# PixiFlood_1_6_PTH.net
KiCad netlist of a schematic drawn in EAGLE
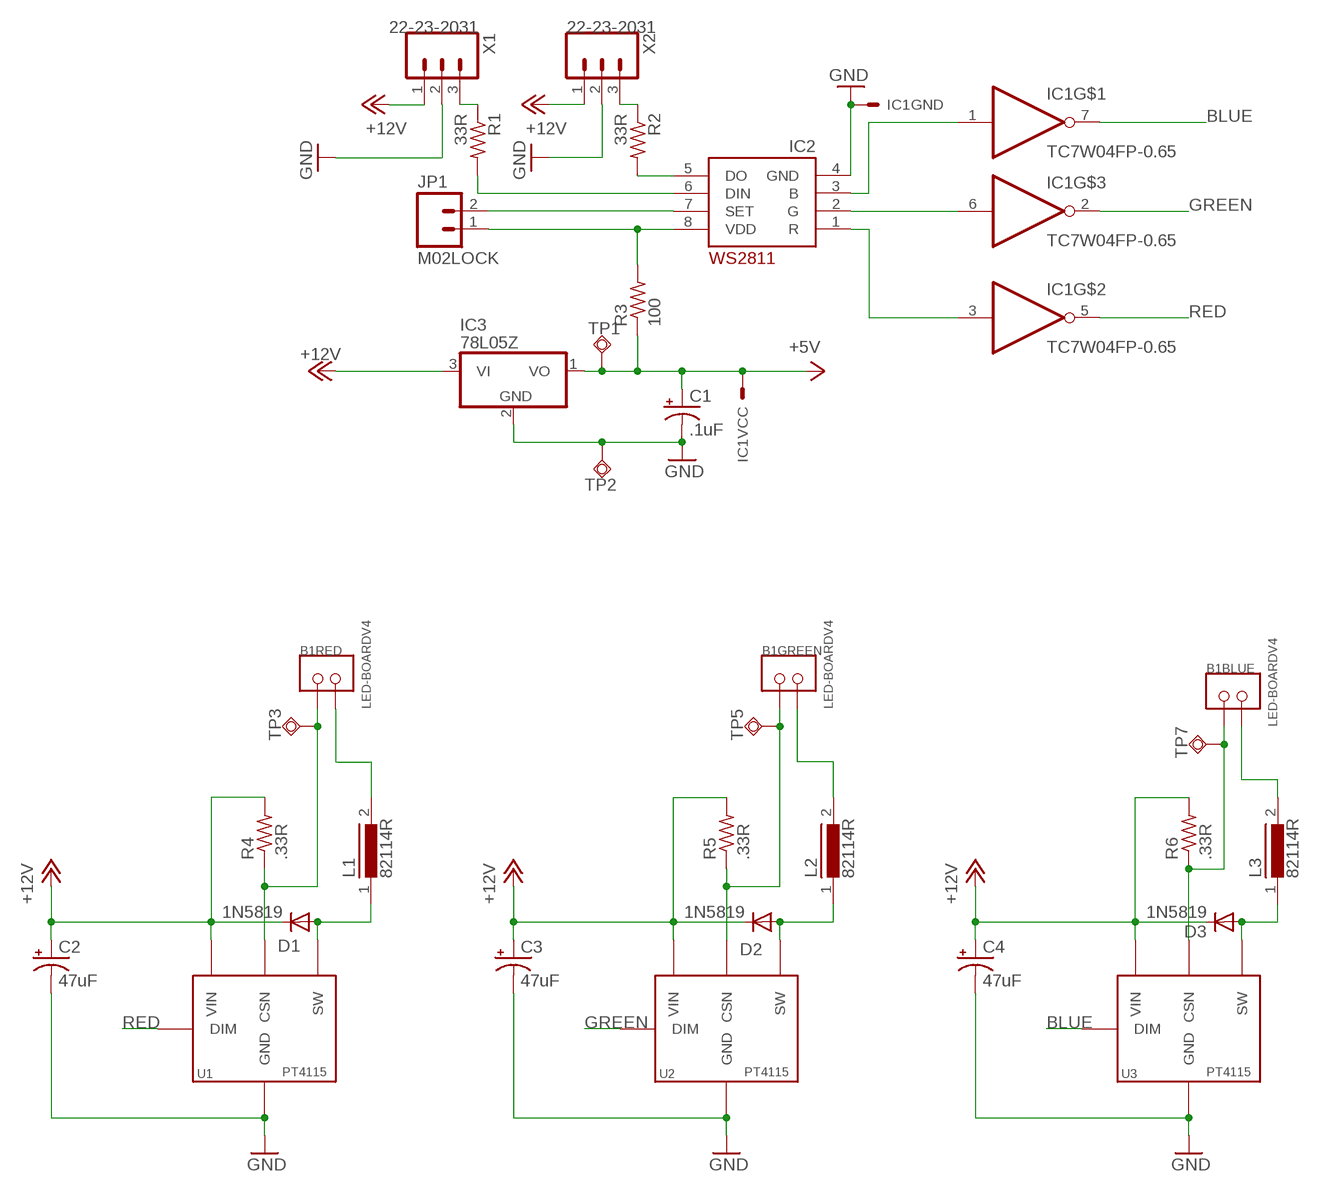
[diagram p0: schematic, sheet 1]

(export (version "E")
  (design (tool "Eeschema 10.0.6"))
  (components
    (comp (ref "B1")
      (value "LED-BOARDV4")
      (footprint "eagle-import:LED_BOARD-V4")
      (libsource (lib "eagle-import") (part "LED-BOARDV4"))
    )
    (comp (ref "C1")
      (value ".1uF")
      (footprint "eagle-import:C025X050P")
      (libsource (lib "eagle-import") (part "CAP_POLPTH50"))
    )
    (comp (ref "C2")
      (value "47uF")
      (footprint "eagle-import:E2,5-5")
      (libsource (lib "eagle-import") (part "CPOL-USE2.5-5"))
    )
    (comp (ref "C3")
      (value "47uF")
      (footprint "eagle-import:E2,5-5")
      (libsource (lib "eagle-import") (part "CPOL-USE2.5-5"))
    )
    (comp (ref "C4")
      (value "47uF")
      (footprint "eagle-import:E2,5-5")
      (libsource (lib "eagle-import") (part "CPOL-USE2.5-5"))
    )
    (comp (ref "D1")
      (value "1N5819")
      (footprint "eagle-import:DO07")
      (libsource (lib "eagle-import") (part "DIODE-DO07"))
    )
    (comp (ref "D2")
      (value "1N5819")
      (footprint "eagle-import:DO07")
      (libsource (lib "eagle-import") (part "DIODE-DO07"))
    )
    (comp (ref "D3")
      (value "1N5819")
      (footprint "eagle-import:DO07")
      (libsource (lib "eagle-import") (part "DIODE-DO07"))
    )
    (comp (ref "IC1")
      (value "TC7W04FP-0.65")
      (footprint "eagle-import:MSOP8")
      (libsource (lib "eagle-import") (part "TC7W04FP-0.65"))
    )
    (comp (ref "IC2")
      (value "WS2811SOP8")
      (footprint "eagle-import:SOP08-P-1.27")
      (libsource (lib "eagle-import") (part "WS2811SOP8"))
    )
    (comp (ref "IC3")
      (value "78L05Z")
      (footprint "eagle-import:TO92")
      (libsource (lib "eagle-import") (part "78ZL05"))
    )
    (comp (ref "JP1")
      (value "M02LOCK")
      (footprint "eagle-import:1X02_LOCK")
      (libsource (lib "eagle-import") (part "M02LOCK"))
    )
    (comp (ref "L1")
      (value "82114R")
      (footprint "eagle-import:82114R")
      (libsource (lib "eagle-import") (part "82114R"))
    )
    (comp (ref "L2")
      (value "82114R")
      (footprint "eagle-import:82114R")
      (libsource (lib "eagle-import") (part "82114R"))
    )
    (comp (ref "L3")
      (value "82114R")
      (footprint "eagle-import:82114R")
      (libsource (lib "eagle-import") (part "82114R"))
    )
    (comp (ref "R1")
      (value "33R")
      (footprint "eagle-import:0204_7")
      (libsource (lib "eagle-import") (part "R-US_0204/7"))
    )
    (comp (ref "R2")
      (value "33R")
      (footprint "eagle-import:0204_7")
      (libsource (lib "eagle-import") (part "R-US_0204/7"))
    )
    (comp (ref "R3")
      (value "100")
      (footprint "eagle-import:0204_7")
      (libsource (lib "eagle-import") (part "R-US_0204/7"))
    )
    (comp (ref "R4")
      (value ".33R")
      (footprint "eagle-import:0204_7")
      (libsource (lib "eagle-import") (part "resistor_R-US_0204/7"))
    )
    (comp (ref "R5")
      (value ".33R")
      (footprint "eagle-import:0204_7")
      (libsource (lib "eagle-import") (part "resistor_R-US_0204/7"))
    )
    (comp (ref "R6")
      (value ".33R")
      (footprint "eagle-import:0204_7")
      (libsource (lib "eagle-import") (part "resistor_R-US_0204/7"))
    )
    (comp (ref "TP1")
      (value "TPSQTP20R")
      (footprint "eagle-import:TP20R")
      (libsource (lib "eagle-import") (part "TPSQTP20R"))
    )
    (comp (ref "TP2")
      (value "TPSQTP20SQ")
      (footprint "eagle-import:TP20SQ")
      (libsource (lib "eagle-import") (part "TPSQTP20SQ"))
    )
    (comp (ref "TP3")
      (value "TPSQTP15R")
      (footprint "eagle-import:TP15R")
      (libsource (lib "eagle-import") (part "TPSQTP15R"))
    )
    (comp (ref "TP5")
      (value "TPSQTP15R")
      (footprint "eagle-import:TP15R")
      (libsource (lib "eagle-import") (part "TPSQTP15R"))
    )
    (comp (ref "TP7")
      (value "TPSQTP15R")
      (footprint "eagle-import:TP15R")
      (libsource (lib "eagle-import") (part "TPSQTP15R"))
    )
    (comp (ref "U1")
      (value "PT4115B89E")
      (footprint "eagle-import:SOT89-5")
      (libsource (lib "eagle-import") (part "PT4115B89E"))
    )
    (comp (ref "U2")
      (value "PT4115B89E")
      (footprint "eagle-import:SOT89-5")
      (libsource (lib "eagle-import") (part "PT4115B89E"))
    )
    (comp (ref "U3")
      (value "PT4115B89E")
      (footprint "eagle-import:SOT89-5")
      (libsource (lib "eagle-import") (part "PT4115B89E"))
    )
    (comp (ref "X1")
      (value "22-23-2031")
      (footprint "eagle-import:22-23-2031")
      (fields (field (name "MF") "MOLEX"))
      (libsource (lib "eagle-import") (part "22-23-2031"))
    )
    (comp (ref "X2")
      (value "22-23-2031")
      (footprint "eagle-import:22-23-2031")
      (fields (field (name "MF") "MOLEX"))
      (libsource (lib "eagle-import") (part "22-23-2031"))
    )
  )
  (nets
    (net (code "1") (name "+5V") (class "Default")
      (node (ref "C1") (pin "1") (pinfunction "+_1") (pintype "passive"))
      (node (ref "IC1") (pin "8") (pinfunction "S_8") (pintype "passive"))
      (node (ref "IC3") (pin "1") (pinfunction "VO_1") (pintype "passive"))
      (node (ref "R3") (pin "1") (pinfunction "1_1") (pintype "passive"))
      (node (ref "TP1") (pin "TP") (pinfunction "TP_TP") (pintype "input"))
    )
    (net (code "2") (name "+12V") (class "Default")
      (node (ref "C2") (pin "+") (pinfunction "+_+") (pintype "passive"))
      (node (ref "C3") (pin "+") (pinfunction "+_+") (pintype "passive"))
      (node (ref "C4") (pin "+") (pinfunction "+_+") (pintype "passive"))
      (node (ref "D1") (pin "C") (pinfunction "C_C") (pintype "passive"))
      (node (ref "D2") (pin "C") (pinfunction "C_C") (pintype "passive"))
      (node (ref "D3") (pin "C") (pinfunction "C_C") (pintype "passive"))
      (node (ref "IC3") (pin "3") (pinfunction "VI_3") (pintype "input"))
      (node (ref "R4") (pin "2") (pinfunction "2_2") (pintype "passive"))
      (node (ref "R5") (pin "2") (pinfunction "2_2") (pintype "passive"))
      (node (ref "R6") (pin "2") (pinfunction "2_2") (pintype "passive"))
      (node (ref "U1") (pin "5") (pinfunction "VIN_5") (pintype "power_in"))
      (node (ref "U2") (pin "5") (pinfunction "VIN_5") (pintype "power_in"))
      (node (ref "U3") (pin "5") (pinfunction "VIN_5") (pintype "power_in"))
      (node (ref "X1") (pin "1") (pinfunction "1_1") (pintype "passive"))
      (node (ref "X2") (pin "1") (pinfunction "1_1") (pintype "passive"))
    )
    (net (code "3") (name "/BLUE") (class "Default")
      (node (ref "IC1") (pin "7") (pinfunction "O_7") (pintype "output"))
      (node (ref "U3") (pin "3") (pinfunction "DIM_3") (pintype "bidirectional"))
    )
    (net (code "4") (name "/GREEN") (class "Default")
      (node (ref "IC1") (pin "2") (pinfunction "O_2") (pintype "output"))
      (node (ref "U2") (pin "3") (pinfunction "DIM_3") (pintype "bidirectional"))
    )
    (net (code "5") (name "/RED") (class "Default")
      (node (ref "IC1") (pin "5") (pinfunction "O_5") (pintype "output"))
      (node (ref "U1") (pin "3") (pinfunction "DIM_3") (pintype "bidirectional"))
    )
    (net (code "6") (name "GND") (class "Default")
      (node (ref "C1") (pin "2") (pinfunction "-_2") (pintype "passive"))
      (node (ref "C2") (pin "-") (pinfunction "-_-") (pintype "passive"))
      (node (ref "C3") (pin "-") (pinfunction "-_-") (pintype "passive"))
      (node (ref "C4") (pin "-") (pinfunction "-_-") (pintype "passive"))
      (node (ref "IC1") (pin "4") (pinfunction "S_4") (pintype "passive"))
      (node (ref "IC2") (pin "4") (pinfunction "GND_4") (pintype "power_in"))
      (node (ref "IC3") (pin "2") (pinfunction "GND_2") (pintype "passive"))
      (node (ref "TP2") (pin "TP") (pinfunction "TP_TP") (pintype "input"))
      (node (ref "U1") (pin "2") (pinfunction "GND_2") (pintype "power_in"))
      (node (ref "U1") (pin "2A") (pinfunction "GND_2A") (pintype "power_in"))
      (node (ref "U1") (pin "2A@1") (pinfunction "GND_2A@1") (pintype "power_in"))
      (node (ref "U1") (pin "2A@2") (pinfunction "GND_2A@2") (pintype "power_in"))
      (node (ref "U1") (pin "2A@3") (pinfunction "GND_2A@3") (pintype "power_in"))
      (node (ref "U1") (pin "2A@4") (pinfunction "GND_2A@4") (pintype "power_in"))
      (node (ref "U2") (pin "2") (pinfunction "GND_2") (pintype "power_in"))
      (node (ref "U2") (pin "2A") (pinfunction "GND_2A") (pintype "power_in"))
      (node (ref "U2") (pin "2A@1") (pinfunction "GND_2A@1") (pintype "power_in"))
      (node (ref "U2") (pin "2A@2") (pinfunction "GND_2A@2") (pintype "power_in"))
      (node (ref "U2") (pin "2A@3") (pinfunction "GND_2A@3") (pintype "power_in"))
      (node (ref "U2") (pin "2A@4") (pinfunction "GND_2A@4") (pintype "power_in"))
      (node (ref "U3") (pin "2") (pinfunction "GND_2") (pintype "power_in"))
      (node (ref "U3") (pin "2A") (pinfunction "GND_2A") (pintype "power_in"))
      (node (ref "U3") (pin "2A@1") (pinfunction "GND_2A@1") (pintype "power_in"))
      (node (ref "U3") (pin "2A@2") (pinfunction "GND_2A@2") (pintype "power_in"))
      (node (ref "U3") (pin "2A@3") (pinfunction "GND_2A@3") (pintype "power_in"))
      (node (ref "U3") (pin "2A@4") (pinfunction "GND_2A@4") (pintype "power_in"))
      (node (ref "X1") (pin "2") (pinfunction "2_2") (pintype "passive"))
      (node (ref "X2") (pin "2") (pinfunction "2_2") (pintype "passive"))
    )
    (net (code "7") (name "Net-(B1A-P$1-PadB-)") (class "Default")
      (node (ref "B1") (pin "B-") (pinfunction "P$1_B-") (pintype "bidirectional"))
      (node (ref "B1") (pin "B-@1") (pinfunction "P$1_B-@1") (pintype "bidirectional"))
      (node (ref "L3") (pin "2") (pinfunction "2_2") (pintype "passive"))
    )
    (net (code "8") (name "Net-(B1B-P$1-PadG-)") (class "Default")
      (node (ref "B1") (pin "G-") (pinfunction "P$1_G-") (pintype "bidirectional"))
      (node (ref "B1") (pin "G-@1") (pinfunction "P$1_G-@1") (pintype "bidirectional"))
      (node (ref "L2") (pin "2") (pinfunction "2_2") (pintype "passive"))
    )
    (net (code "9") (name "Net-(B1C-P$1-PadR-)") (class "Default")
      (node (ref "B1") (pin "R-") (pinfunction "P$1_R-") (pintype "bidirectional"))
      (node (ref "B1") (pin "R-@1") (pinfunction "P$1_R-@1") (pintype "bidirectional"))
      (node (ref "L1") (pin "2") (pinfunction "2_2") (pintype "passive"))
    )
    (net (code "10") (name "Net-(IC1A-I)") (class "Default")
      (node (ref "IC1") (pin "1") (pinfunction "I_1") (pintype "input"))
      (node (ref "IC2") (pin "3") (pinfunction "B_3") (pintype "open_collector"))
    )
    (net (code "11") (name "Net-(IC1B-I)") (class "Default")
      (node (ref "IC1") (pin "3") (pinfunction "I_3") (pintype "input"))
      (node (ref "IC2") (pin "1") (pinfunction "R_1") (pintype "open_collector"))
    )
    (net (code "12") (name "Net-(IC1C-I)") (class "Default")
      (node (ref "IC1") (pin "6") (pinfunction "I_6") (pintype "input"))
      (node (ref "IC2") (pin "2") (pinfunction "G_2") (pintype "open_collector"))
    )
    (net (code "13") (name "Net-(IC2-DIN)") (class "Default")
      (node (ref "IC2") (pin "6") (pinfunction "DIN_6") (pintype "input"))
      (node (ref "R1") (pin "2") (pinfunction "2_2") (pintype "passive"))
    )
    (net (code "14") (name "Net-(IC2-DO)") (class "Default")
      (node (ref "IC2") (pin "5") (pinfunction "DO_5") (pintype "output"))
      (node (ref "R2") (pin "2") (pinfunction "2_2") (pintype "passive"))
    )
    (net (code "15") (name "Net-(IC2-SET)") (class "Default")
      (node (ref "IC2") (pin "7") (pinfunction "SET_7") (pintype "input"))
      (node (ref "JP1") (pin "2") (pinfunction "2_2") (pintype "passive"))
    )
    (net (code "16") (name "Net-(IC2-VDD)") (class "Default")
      (node (ref "IC2") (pin "8") (pinfunction "VDD_8") (pintype "power_in"))
      (node (ref "JP1") (pin "1") (pinfunction "1_1") (pintype "passive"))
      (node (ref "R3") (pin "2") (pinfunction "2_2") (pintype "passive"))
    )
    (net (code "17") (name "Net-(R1-Pad1)") (class "Default")
      (node (ref "R1") (pin "1") (pinfunction "1_1") (pintype "passive"))
      (node (ref "X1") (pin "3") (pinfunction "3_3") (pintype "passive"))
    )
    (net (code "18") (name "Net-(R2-Pad1)") (class "Default")
      (node (ref "R2") (pin "1") (pinfunction "1_1") (pintype "passive"))
      (node (ref "X2") (pin "3") (pinfunction "3_3") (pintype "passive"))
    )
    (net (code "19") (name "Net-(U1-CSN)") (class "Default")
      (node (ref "B1") (pin "R+") (pinfunction "P$2_R+") (pintype "bidirectional"))
      (node (ref "B1") (pin "R+@1") (pinfunction "P$2_R+@1") (pintype "bidirectional"))
      (node (ref "R4") (pin "1") (pinfunction "1_1") (pintype "passive"))
      (node (ref "TP3") (pin "TP") (pinfunction "TP_TP") (pintype "input"))
      (node (ref "U1") (pin "4") (pinfunction "CSN_4") (pintype "bidirectional"))
    )
    (net (code "20") (name "Net-(U1-SW)") (class "Default")
      (node (ref "D1") (pin "A") (pinfunction "A_A") (pintype "passive"))
      (node (ref "L1") (pin "1") (pinfunction "1_1") (pintype "passive"))
      (node (ref "U1") (pin "1") (pinfunction "SW_1") (pintype "bidirectional"))
    )
    (net (code "21") (name "Net-(U2-CSN)") (class "Default")
      (node (ref "B1") (pin "G+") (pinfunction "P$2_G+") (pintype "bidirectional"))
      (node (ref "B1") (pin "G+@1") (pinfunction "P$2_G+@1") (pintype "bidirectional"))
      (node (ref "R5") (pin "1") (pinfunction "1_1") (pintype "passive"))
      (node (ref "TP5") (pin "TP") (pinfunction "TP_TP") (pintype "input"))
      (node (ref "U2") (pin "4") (pinfunction "CSN_4") (pintype "bidirectional"))
    )
    (net (code "22") (name "Net-(U2-SW)") (class "Default")
      (node (ref "D2") (pin "A") (pinfunction "A_A") (pintype "passive"))
      (node (ref "L2") (pin "1") (pinfunction "1_1") (pintype "passive"))
      (node (ref "U2") (pin "1") (pinfunction "SW_1") (pintype "bidirectional"))
    )
    (net (code "23") (name "Net-(U3-CSN)") (class "Default")
      (node (ref "B1") (pin "B+") (pinfunction "P$2_B+") (pintype "bidirectional"))
      (node (ref "B1") (pin "B+@2") (pinfunction "P$2_B+@2") (pintype "bidirectional"))
      (node (ref "R6") (pin "1") (pinfunction "1_1") (pintype "passive"))
      (node (ref "TP7") (pin "TP") (pinfunction "TP_TP") (pintype "input"))
      (node (ref "U3") (pin "4") (pinfunction "CSN_4") (pintype "bidirectional"))
    )
    (net (code "24") (name "Net-(U3-SW)") (class "Default")
      (node (ref "D3") (pin "A") (pinfunction "A_A") (pintype "passive"))
      (node (ref "L3") (pin "1") (pinfunction "1_1") (pintype "passive"))
      (node (ref "U3") (pin "1") (pinfunction "SW_1") (pintype "bidirectional"))
    )
  )
)
